# 3_IMU.net
KiCad netlist of a schematic drawn in Altium Designer
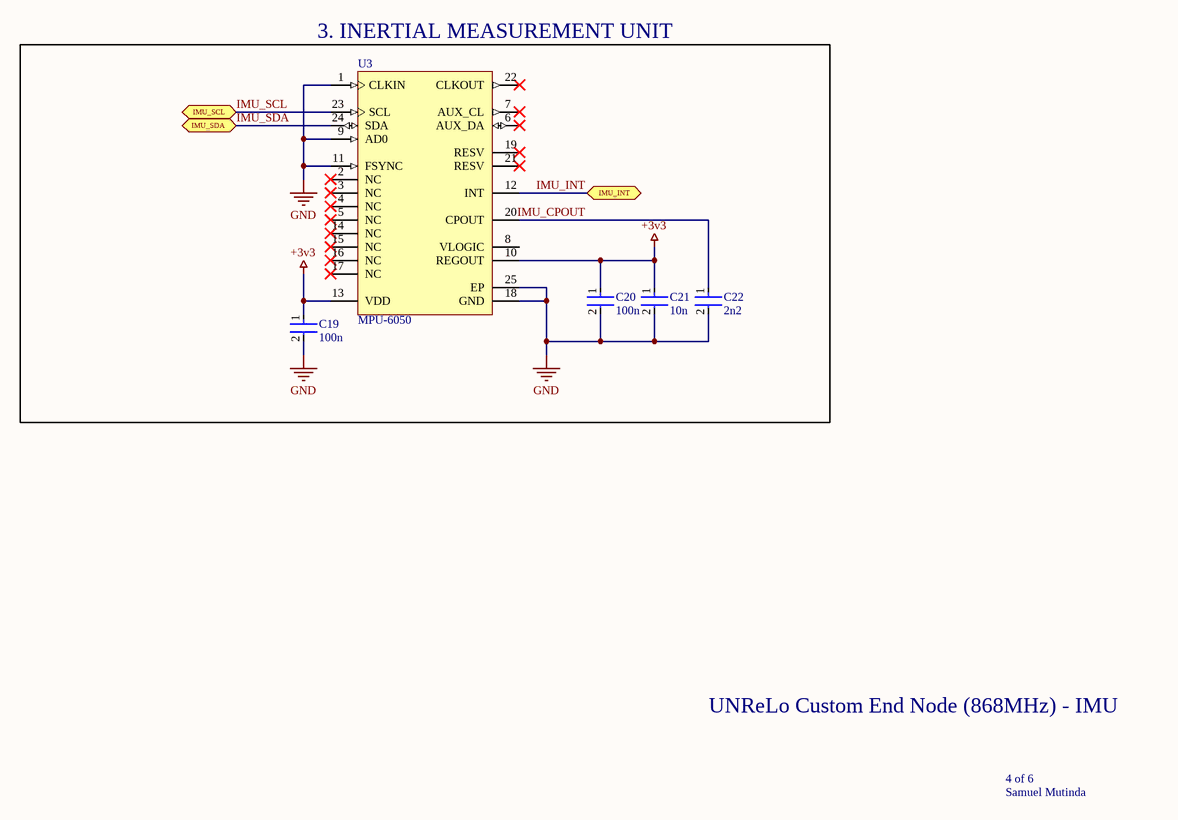
[diagram p0: 3_IMU.SchDoc]

(export (version "E")
  (design (tool "Eeschema 10.0.6"))
  (components
    (comp (ref "C19")
      (value "100n")
      (footprint "FP-C0402-BB-MFG")
      (description "CAP CER 0.1UF 16V 5% X7R 0402")
      (fields
        (field (name "OCTOPART") "https://octopart.com/c0402c104j4ractu-kemet-12573893")
        (field (name "TOLERANCE") "0.05")
      )
      (libsource (lib "Altium Content Vault") (part "b4654b650e69147ec39a6b967a45e02"))
    )
    (comp (ref "C20")
      (value "100n")
      (footprint "FP-C0402-BB-MFG")
      (description "CAP CER 0.1UF 16V 5% X7R 0402")
      (fields
        (field (name "MANUFACTURER PART NUMBER") "C0402C104J4RACTU")
        (field (name "OCTOPART") "https://octopart.com/c0402c104j4ractu-kemet-12573893")
      )
      (libsource (lib "Altium Content Vault") (part "b4654b650e69147ec39a6b967a45e02"))
    )
    (comp (ref "C21")
      (value "10n")
      (footprint "FP-C0402-BB-MFG")
      (description "CAP CER 0402 10NF 50V X7R 5%")
      (fields
        (field (name "MANUFACTURER PART NUMBER") "C0402C104J4RACTU")
        (field (name "OCTOPART") "https://octopart.com/c0402c104j4ractu-kemet-12573893")
      )
      (libsource (lib "Altium Content Vault") (part "b4654b650e69147ec39a6b967a45e02"))
    )
    (comp (ref "C22")
      (value "2n2")
      (footprint "FP-C0402-BB-MFG")
      (description "CAP CER 0.1UF 16V 5% X7R 0402")
      (fields
        (field (name "OCTOPART") "https://octopart.com/c0402c104j4ractu-kemet-12573893")
        (field (name "TOLERANCE") "0.05")
      )
      (libsource (lib "Altium Content Vault") (part "b4654b650e69147ec39a6b967a45e02"))
    )
    (comp (ref "U3")
      (value "MPU-6050")
      (footprint "IS-QFN-24_V")
      (libsource (lib "Altium Content Vault") (part "IS-MPU-6050-QFN-24"))
    )
  )
  (nets
    (net (code "1") (name "+3v3") (class "Default")
      (node (ref "C19") (pin "1") (pinfunction "1_1") (pintype "passive"))
      (node (ref "C20") (pin "1") (pinfunction "1_1") (pintype "passive"))
      (node (ref "C21") (pin "1") (pinfunction "1_1") (pintype "passive"))
      (node (ref "U3") (pin "10") (pinfunction "REGOUT_10") (pintype "passive"))
      (node (ref "U3") (pin "13") (pinfunction "VDD_13") (pintype "power_in"))
    )
    (net (code "2") (name "/IMU_CPOUT") (class "Default")
      (node (ref "C22") (pin "1") (pinfunction "1_1") (pintype "passive"))
      (node (ref "U3") (pin "20") (pinfunction "CPOUT_20") (pintype "passive"))
    )
    (net (code "3") (name "/IMU_INT") (class "Default")
      (node (ref "U3") (pin "12") (pinfunction "INT_12") (pintype "open_collector"))
    )
    (net (code "4") (name "/IMU_SCL") (class "Default")
      (node (ref "U3") (pin "23") (pinfunction "SCL_23") (pintype "input"))
    )
    (net (code "5") (name "/IMU_SDA") (class "Default")
      (node (ref "U3") (pin "24") (pinfunction "SDA_24") (pintype "bidirectional"))
    )
    (net (code "6") (name "GND") (class "Default")
      (node (ref "C19") (pin "2") (pinfunction "2_2") (pintype "passive"))
      (node (ref "C20") (pin "2") (pinfunction "2_2") (pintype "passive"))
      (node (ref "C21") (pin "2") (pinfunction "2_2") (pintype "passive"))
      (node (ref "C22") (pin "2") (pinfunction "2_2") (pintype "passive"))
      (node (ref "U3") (pin "1") (pinfunction "CLKIN_1") (pintype "input"))
      (node (ref "U3") (pin "11") (pinfunction "FSYNC_11") (pintype "input"))
      (node (ref "U3") (pin "18") (pinfunction "GND_18") (pintype "power_in"))
      (node (ref "U3") (pin "25") (pinfunction "EP_25") (pintype "power_in"))
      (node (ref "U3") (pin "9") (pinfunction "AD0_9") (pintype "input"))
    )
    (net (code "7") (name "unconnected-(U3-AUX_CL-Pad7)") (class "Default")
      (node (ref "U3") (pin "7") (pinfunction "AUX_CL_7") (pintype "output+no_connect"))
    )
    (net (code "8") (name "unconnected-(U3-AUX_DA-Pad6)") (class "Default")
      (node (ref "U3") (pin "6") (pinfunction "AUX_DA_6") (pintype "bidirectional+no_connect"))
    )
    (net (code "9") (name "unconnected-(U3-CLKOUT-Pad22)") (class "Default")
      (node (ref "U3") (pin "22") (pinfunction "CLKOUT_22") (pintype "output+no_connect"))
    )
    (net (code "10") (name "unconnected-(U3-NC-Pad2)") (class "Default")
      (node (ref "U3") (pin "2") (pinfunction "NC_2") (pintype "passive+no_connect"))
    )
    (net (code "11") (name "unconnected-(U3-NC-Pad3)") (class "Default")
      (node (ref "U3") (pin "3") (pinfunction "NC_3") (pintype "passive+no_connect"))
    )
    (net (code "12") (name "unconnected-(U3-NC-Pad4)") (class "Default")
      (node (ref "U3") (pin "4") (pinfunction "NC_4") (pintype "passive+no_connect"))
    )
    (net (code "13") (name "unconnected-(U3-NC-Pad5)") (class "Default")
      (node (ref "U3") (pin "5") (pinfunction "NC_5") (pintype "passive+no_connect"))
    )
    (net (code "14") (name "unconnected-(U3-NC-Pad14)") (class "Default")
      (node (ref "U3") (pin "14") (pinfunction "NC_14") (pintype "passive+no_connect"))
    )
    (net (code "15") (name "unconnected-(U3-NC-Pad15)") (class "Default")
      (node (ref "U3") (pin "15") (pinfunction "NC_15") (pintype "passive+no_connect"))
    )
    (net (code "16") (name "unconnected-(U3-NC-Pad16)") (class "Default")
      (node (ref "U3") (pin "16") (pinfunction "NC_16") (pintype "passive+no_connect"))
    )
    (net (code "17") (name "unconnected-(U3-NC-Pad17)") (class "Default")
      (node (ref "U3") (pin "17") (pinfunction "NC_17") (pintype "passive+no_connect"))
    )
    (net (code "18") (name "unconnected-(U3-RESV-Pad19)") (class "Default")
      (node (ref "U3") (pin "19") (pinfunction "RESV_19") (pintype "passive+no_connect"))
    )
    (net (code "19") (name "unconnected-(U3-RESV-Pad21)") (class "Default")
      (node (ref "U3") (pin "21") (pinfunction "RESV_21") (pintype "passive+no_connect"))
    )
    (net (code "20") (name "unconnected-(U3-VLOGIC-Pad8)") (class "Default")
      (node (ref "U3") (pin "8") (pinfunction "VLOGIC_8") (pintype "power_in"))
    )
  )
)
